# Grove_-_Recorder_v2_0.net
KiCad netlist of a schematic drawn in EAGLE
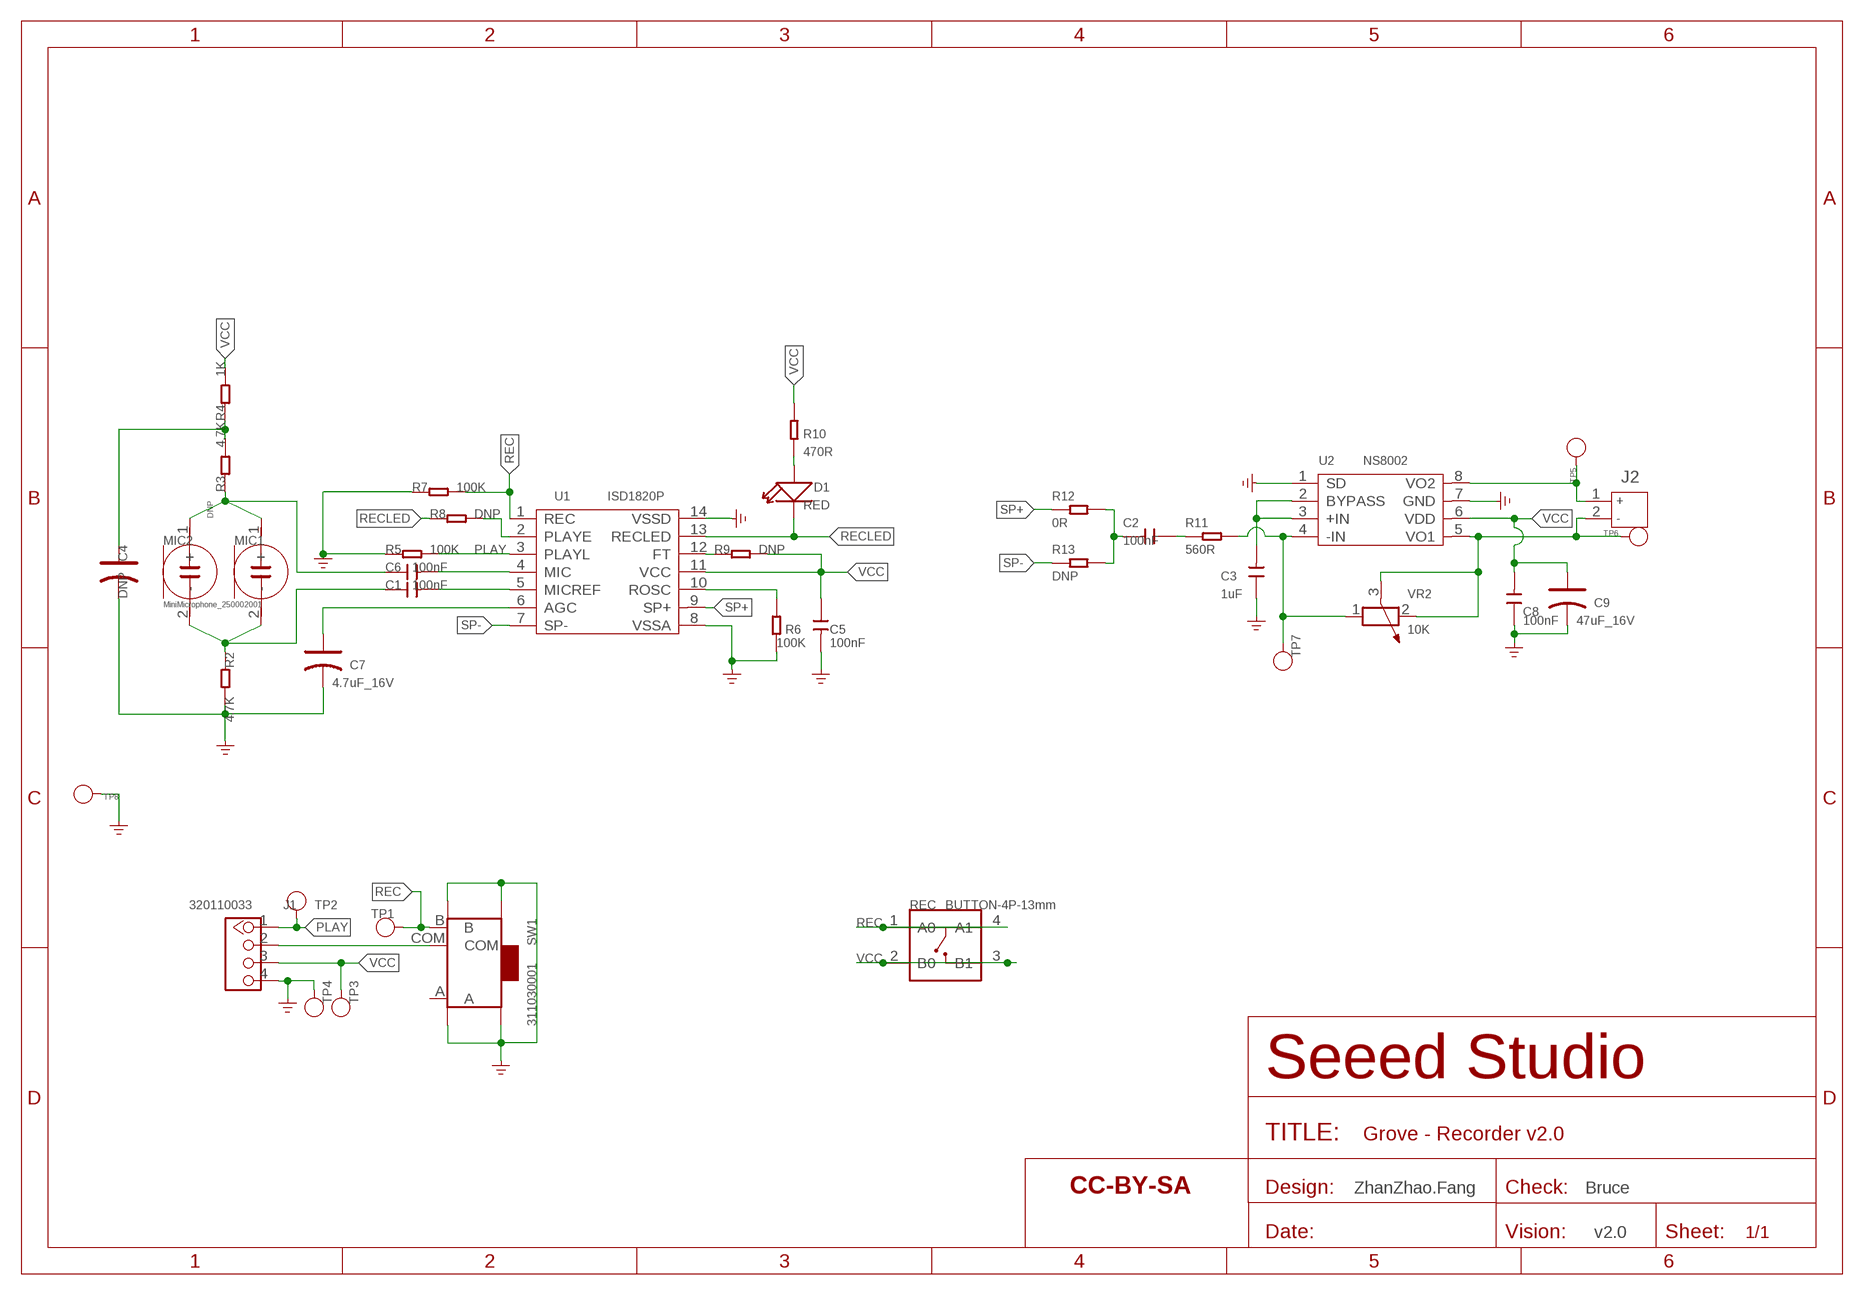
[diagram p0: schematic, sheet 1]

(export (version "E")
  (design (tool "Eeschema 10.0.6"))
  (components
    (comp (ref "C1")
      (value "100nF")
      (footprint "eagle-import:C0402")
      (libsource (lib "eagle-import") (part "C-0402"))
    )
    (comp (ref "C2")
      (value "100nF")
      (footprint "eagle-import:C0603")
      (libsource (lib "eagle-import") (part "CAP-0603"))
    )
    (comp (ref "C3")
      (value "1uF")
      (footprint "eagle-import:C0402")
      (libsource (lib "eagle-import") (part "CAP-0402"))
    )
    (comp (ref "C4")
      (value "DNP")
      (footprint "eagle-import:AVX-A")
      (libsource (lib "eagle-import") (part "CAP-AVX-A"))
    )
    (comp (ref "C5")
      (value "100nF")
      (footprint "eagle-import:C0402")
      (libsource (lib "eagle-import") (part "C-0402"))
    )
    (comp (ref "C6")
      (value "100nF")
      (footprint "eagle-import:C0402")
      (libsource (lib "eagle-import") (part "C-0402"))
    )
    (comp (ref "C7")
      (value "4.7uF_16V")
      (footprint "eagle-import:AVX-A")
      (libsource (lib "eagle-import") (part "C-POLAR-A"))
    )
    (comp (ref "C8")
      (value "100nF")
      (footprint "eagle-import:C0402")
      (libsource (lib "eagle-import") (part "CAP-0402"))
    )
    (comp (ref "C9")
      (value "47uF_16V")
      (footprint "eagle-import:AVX-B")
      (libsource (lib "eagle-import") (part "C-POLAR-B"))
    )
    (comp (ref "D1")
      (value "RED")
      (footprint "eagle-import:LED-SIDE-VIEW-0603-RIGHT")
      (libsource (lib "eagle-import") (part "LED'RIGHT'"))
    )
    (comp (ref "FR1")
      (value "SEEEDSTUDIO-OPEN-SCH-FRAME")
      (footprint "eagle-import:SEEEDSTUDIO-PCB-FRAME")
      (libsource (lib "eagle-import") (part "SEEEDSTUDIO-OPEN-SCH-FRAME"))
    )
    (comp (ref "J1")
      (value "320110033")
      (footprint "eagle-import:HW4-2.0")
      (libsource (lib "eagle-import") (part "GROVE-CONNECTOR-DIP-2.0"))
    )
    (comp (ref "J2")
      (value "2P-2.0")
      (footprint "eagle-import:JST-2.0")
      (libsource (lib "eagle-import") (part "JACK-JST-2P-PW'2.0'"))
    )
    (comp (ref "MIC1")
      (value "MiniMicrophone_250002001")
      (footprint "eagle-import:2P-D8.9MM")
      (libsource (lib "eagle-import") (part "MICROPHONE"))
    )
    (comp (ref "MIC2")
      (value "DNP")
      (footprint "eagle-import:2P-D8.9MM")
      (libsource (lib "eagle-import") (part "MICROPHONE"))
    )
    (comp (ref "R2")
      (value "4.7K")
      (footprint "eagle-import:R0402")
      (libsource (lib "eagle-import") (part "R-0402"))
    )
    (comp (ref "R3")
      (value "4.7K")
      (footprint "eagle-import:R0402")
      (libsource (lib "eagle-import") (part "R-0402"))
    )
    (comp (ref "R4")
      (value "1K")
      (footprint "eagle-import:R0402")
      (libsource (lib "eagle-import") (part "R-0402"))
    )
    (comp (ref "R5")
      (value "100K")
      (footprint "eagle-import:R0402")
      (libsource (lib "eagle-import") (part "R-0402"))
    )
    (comp (ref "R6")
      (value "100K")
      (footprint "eagle-import:R0402")
      (libsource (lib "eagle-import") (part "R-0402"))
    )
    (comp (ref "R7")
      (value "100K")
      (footprint "eagle-import:R0402")
      (libsource (lib "eagle-import") (part "R-0402"))
    )
    (comp (ref "R8")
      (value "DNP")
      (footprint "eagle-import:R0402")
      (libsource (lib "eagle-import") (part "R-0402"))
    )
    (comp (ref "R9")
      (value "DNP")
      (footprint "eagle-import:R0402")
      (libsource (lib "eagle-import") (part "R-0402"))
    )
    (comp (ref "R10")
      (value "470R")
      (footprint "eagle-import:R0402")
      (libsource (lib "eagle-import") (part "R-0402"))
    )
    (comp (ref "R11")
      (value "560R")
      (footprint "eagle-import:R0402")
      (libsource (lib "eagle-import") (part "RES-0402"))
    )
    (comp (ref "R12")
      (value "0R")
      (footprint "eagle-import:R0402")
      (libsource (lib "eagle-import") (part "R-0402"))
    )
    (comp (ref "R13")
      (value "DNP")
      (footprint "eagle-import:R0402")
      (libsource (lib "eagle-import") (part "R-0402"))
    )
    (comp (ref "REC")
      (value "BUTTON-4P-13mm")
      (footprint "eagle-import:4P-6.0X6.0X5.0H")
      (libsource (lib "eagle-import") (part "BUTTON-4P-3110040P1"))
    )
    (comp (ref "SW1")
      (value "311030001")
      (footprint "eagle-import:SW7-SMD-L6.7X2.7X3.2MM")
      (libsource (lib "eagle-import") (part "SWITCH-3+4P"))
    )
    (comp (ref "TP1")
      (value "DNP")
      (footprint "eagle-import:TP-D45MIL")
      (libsource (lib "eagle-import") (part "TEST-POINT'4545'"))
    )
    (comp (ref "TP2")
      (value "DNP")
      (footprint "eagle-import:TP-D45MIL")
      (libsource (lib "eagle-import") (part "TEST-POINT'4545'"))
    )
    (comp (ref "TP3")
      (value "DNP")
      (footprint "eagle-import:TP-D45MIL")
      (libsource (lib "eagle-import") (part "TEST-POINT'4545'"))
    )
    (comp (ref "TP4")
      (value "DNP")
      (footprint "eagle-import:TP-D45MIL")
      (libsource (lib "eagle-import") (part "TEST-POINT'4545'"))
    )
    (comp (ref "TP5")
      (value "DNP")
      (footprint "eagle-import:TP_4545")
      (libsource (lib "eagle-import") (part "PAD-TEST-POINT'4545'"))
    )
    (comp (ref "TP6")
      (value "DNP")
      (footprint "eagle-import:TP_4545")
      (libsource (lib "eagle-import") (part "PAD-TEST-POINT'4545'"))
    )
    (comp (ref "TP7")
      (value "DNP")
      (footprint "eagle-import:TP-D45MIL")
      (libsource (lib "eagle-import") (part "TEST-POINT'4545'"))
    )
    (comp (ref "TP8")
      (value "DNP")
      (footprint "eagle-import:TP_4545")
      (libsource (lib "eagle-import") (part "PAD-TEST-POINT'4545'"))
    )
    (comp (ref "U1")
      (value "ISD1820P")
      (footprint "eagle-import:DIP14")
      (libsource (lib "eagle-import") (part "ISD1820P"))
    )
    (comp (ref "U2")
      (value "NS8002")
      (footprint "eagle-import:SOIC8-1.27-5X4MM")
      (libsource (lib "eagle-import") (part "AMPLIFIER-NS8002"))
    )
    (comp (ref "VR2")
      (value "10K")
      (footprint "eagle-import:ADJR3-7.0X7.0X5.0MM")
      (libsource (lib "eagle-import") (part "RES-ADJ-SX3362P"))
    )
  )
  (nets
    (net (code "1") (name "GND_POWER") (class "Default")
      (node (ref "C3") (pin "1") (pinfunction "1_1") (pintype "passive"))
      (node (ref "C4") (pin "-") (pinfunction "-_-") (pintype "passive"))
      (node (ref "C5") (pin "2") (pinfunction "2_2") (pintype "passive"))
      (node (ref "C7") (pin "-") (pinfunction "2_-") (pintype "bidirectional"))
      (node (ref "C8") (pin "1") (pinfunction "1_1") (pintype "passive"))
      (node (ref "C9") (pin "-") (pinfunction "2_-") (pintype "bidirectional"))
      (node (ref "J1") (pin "4") (pinfunction "4_4") (pintype "bidirectional"))
      (node (ref "R2") (pin "2") (pinfunction "2_2") (pintype "passive"))
      (node (ref "R5") (pin "1") (pinfunction "1_1") (pintype "passive"))
      (node (ref "R6") (pin "1") (pinfunction "1_1") (pintype "passive"))
      (node (ref "R7") (pin "1") (pinfunction "1_1") (pintype "passive"))
      (node (ref "SW1") (pin "SS1") (pinfunction "SS1_SS1") (pintype "bidirectional"))
      (node (ref "SW1") (pin "SS2") (pinfunction "SS2_SS2") (pintype "bidirectional"))
      (node (ref "SW1") (pin "SS3") (pinfunction "SS3_SS3") (pintype "bidirectional"))
      (node (ref "SW1") (pin "SS4") (pinfunction "SS4_SS4") (pintype "bidirectional"))
      (node (ref "TP4") (pin "T") (pinfunction "T_T") (pintype "bidirectional"))
      (node (ref "TP8") (pin "T") (pinfunction "T_T") (pintype "bidirectional"))
      (node (ref "U1") (pin "14") (pinfunction "VSSD_14") (pintype "bidirectional"))
      (node (ref "U1") (pin "8") (pinfunction "VSSA_8") (pintype "bidirectional"))
      (node (ref "U2") (pin "1") (pinfunction "SD_1") (pintype "bidirectional"))
      (node (ref "U2") (pin "7") (pinfunction "GND_7") (pintype "power_in"))
    )
    (net (code "2") (name "Net-(C2-Pad1)") (class "Default")
      (node (ref "C2") (pin "1") (pinfunction "1_1") (pintype "passive"))
      (node (ref "R11") (pin "1") (pinfunction "1_1") (pintype "passive"))
    )
    (net (code "3") (name "Net-(C2-Pad2)") (class "Default")
      (node (ref "C2") (pin "2") (pinfunction "2_2") (pintype "passive"))
      (node (ref "R12") (pin "1") (pinfunction "1_1") (pintype "passive"))
      (node (ref "R13") (pin "1") (pinfunction "1_1") (pintype "passive"))
    )
    (net (code "4") (name "Net-(C4-Pad+)") (class "Default")
      (node (ref "C4") (pin "+") (pinfunction "+_+") (pintype "passive"))
      (node (ref "R3") (pin "2") (pinfunction "2_2") (pintype "passive"))
      (node (ref "R4") (pin "1") (pinfunction "1_1") (pintype "passive"))
    )
    (net (code "5") (name "Net-(C7-1)") (class "Default")
      (node (ref "C7") (pin "+") (pinfunction "1_+") (pintype "bidirectional"))
      (node (ref "U1") (pin "6") (pinfunction "AGC_6") (pintype "bidirectional"))
    )
    (net (code "6") (name "Net-(D1-+)") (class "Default")
      (node (ref "D1") (pin "1") (pinfunction "+_1") (pintype "passive"))
      (node (ref "R10") (pin "1") (pinfunction "1_1") (pintype "passive"))
    )
    (net (code "7") (name "Net-(J1-Pad2)") (class "Default")
      (node (ref "J1") (pin "2") (pinfunction "2_2") (pintype "bidirectional"))
      (node (ref "SW1") (pin "COM") (pinfunction "COM_COM") (pintype "bidirectional"))
    )
    (net (code "8") (name "Net-(J2-P$1)") (class "Default")
      (node (ref "J2") (pin "1") (pinfunction "P$1_1") (pintype "bidirectional"))
      (node (ref "TP5") (pin "T") (pinfunction "T_T") (pintype "bidirectional"))
      (node (ref "U2") (pin "8") (pinfunction "VO2_8") (pintype "output"))
    )
    (net (code "9") (name "Net-(J2-P$2)") (class "Default")
      (node (ref "J2") (pin "2") (pinfunction "P$2_2") (pintype "bidirectional"))
      (node (ref "TP6") (pin "T") (pinfunction "T_T") (pintype "bidirectional"))
      (node (ref "U2") (pin "5") (pinfunction "VO1_5") (pintype "output"))
      (node (ref "VR2") (pin "2") (pinfunction "2_2") (pintype "passive"))
      (node (ref "VR2") (pin "3") (pinfunction "3_3") (pintype "passive"))
    )
    (net (code "10") (name "Net-(MIC1-+)") (class "Default")
      (node (ref "C6") (pin "1") (pinfunction "1_1") (pintype "passive"))
      (node (ref "MIC1") (pin "1") (pinfunction "+_1") (pintype "bidirectional"))
      (node (ref "MIC2") (pin "1") (pinfunction "+_1") (pintype "bidirectional"))
      (node (ref "R3") (pin "1") (pinfunction "1_1") (pintype "passive"))
    )
    (net (code "11") (name "Net-(MIC1--)") (class "Default")
      (node (ref "C1") (pin "1") (pinfunction "1_1") (pintype "passive"))
      (node (ref "MIC1") (pin "2") (pinfunction "-_2") (pintype "bidirectional"))
      (node (ref "MIC2") (pin "2") (pinfunction "-_2") (pintype "bidirectional"))
      (node (ref "R2") (pin "1") (pinfunction "1_1") (pintype "passive"))
    )
    (net (code "12") (name "Net-(U1-FT)") (class "Default")
      (node (ref "R9") (pin "1") (pinfunction "1_1") (pintype "passive"))
      (node (ref "U1") (pin "12") (pinfunction "FT_12") (pintype "bidirectional"))
    )
    (net (code "13") (name "Net-(U1-MIC)") (class "Default")
      (node (ref "C6") (pin "2") (pinfunction "2_2") (pintype "passive"))
      (node (ref "U1") (pin "4") (pinfunction "MIC_4") (pintype "bidirectional"))
    )
    (net (code "14") (name "Net-(U1-MICREF)") (class "Default")
      (node (ref "C1") (pin "2") (pinfunction "2_2") (pintype "passive"))
      (node (ref "U1") (pin "5") (pinfunction "MICREF_5") (pintype "bidirectional"))
    )
    (net (code "15") (name "Net-(U1-PLAYE)") (class "Default")
      (node (ref "R8") (pin "2") (pinfunction "2_2") (pintype "passive"))
      (node (ref "U1") (pin "2") (pinfunction "PLAYE_2") (pintype "bidirectional"))
    )
    (net (code "16") (name "Net-(U1-ROSC)") (class "Default")
      (node (ref "R6") (pin "2") (pinfunction "2_2") (pintype "passive"))
      (node (ref "U1") (pin "10") (pinfunction "ROSC_10") (pintype "bidirectional"))
    )
    (net (code "17") (name "Net-(U2-+IN)") (class "Default")
      (node (ref "C3") (pin "2") (pinfunction "2_2") (pintype "passive"))
      (node (ref "U2") (pin "2") (pinfunction "BYPASS_2") (pintype "bidirectional"))
      (node (ref "U2") (pin "3") (pinfunction "+IN_3") (pintype "input"))
    )
    (net (code "18") (name "Net-(U2--IN)") (class "Default")
      (node (ref "R11") (pin "2") (pinfunction "2_2") (pintype "passive"))
      (node (ref "TP7") (pin "T") (pinfunction "T_T") (pintype "bidirectional"))
      (node (ref "U2") (pin "4") (pinfunction "-IN_4") (pintype "input"))
      (node (ref "VR2") (pin "1") (pinfunction "1_1") (pintype "passive"))
    )
    (net (code "19") (name "PLAY") (class "Default")
      (node (ref "J1") (pin "1") (pinfunction "1_1") (pintype "bidirectional"))
      (node (ref "R5") (pin "2") (pinfunction "2_2") (pintype "passive"))
      (node (ref "TP2") (pin "T") (pinfunction "T_T") (pintype "bidirectional"))
      (node (ref "U1") (pin "3") (pinfunction "PLAYL_3") (pintype "bidirectional"))
    )
    (net (code "20") (name "REC") (class "Default")
      (node (ref "R7") (pin "2") (pinfunction "2_2") (pintype "passive"))
      (node (ref "REC") (pin "1") (pinfunction "A0_1") (pintype "bidirectional"))
      (node (ref "REC") (pin "4") (pinfunction "A1_4") (pintype "bidirectional"))
      (node (ref "SW1") (pin "B") (pinfunction "B_B") (pintype "bidirectional"))
      (node (ref "TP1") (pin "T") (pinfunction "T_T") (pintype "bidirectional"))
      (node (ref "U1") (pin "1") (pinfunction "REC_1") (pintype "bidirectional"))
    )
    (net (code "21") (name "RECLED") (class "Default")
      (node (ref "D1") (pin "2") (pinfunction "-_2") (pintype "passive"))
      (node (ref "R8") (pin "1") (pinfunction "1_1") (pintype "passive"))
      (node (ref "U1") (pin "13") (pinfunction "RECLED_13") (pintype "bidirectional"))
    )
    (net (code "22") (name "SP+") (class "Default")
      (node (ref "R12") (pin "2") (pinfunction "2_2") (pintype "passive"))
      (node (ref "U1") (pin "9") (pinfunction "SP+_9") (pintype "bidirectional"))
    )
    (net (code "23") (name "SP-") (class "Default")
      (node (ref "R13") (pin "2") (pinfunction "2_2") (pintype "passive"))
      (node (ref "U1") (pin "7") (pinfunction "SP-_7") (pintype "bidirectional"))
    )
    (net (code "24") (name "VCC") (class "Default")
      (node (ref "C5") (pin "1") (pinfunction "1_1") (pintype "passive"))
      (node (ref "C8") (pin "2") (pinfunction "2_2") (pintype "passive"))
      (node (ref "C9") (pin "+") (pinfunction "1_+") (pintype "bidirectional"))
      (node (ref "J1") (pin "3") (pinfunction "3_3") (pintype "bidirectional"))
      (node (ref "R10") (pin "2") (pinfunction "2_2") (pintype "passive"))
      (node (ref "R4") (pin "2") (pinfunction "2_2") (pintype "passive"))
      (node (ref "R9") (pin "2") (pinfunction "2_2") (pintype "passive"))
      (node (ref "REC") (pin "2") (pinfunction "B0_2") (pintype "bidirectional"))
      (node (ref "REC") (pin "3") (pinfunction "B1_3") (pintype "bidirectional"))
      (node (ref "TP3") (pin "T") (pinfunction "T_T") (pintype "bidirectional"))
      (node (ref "U1") (pin "11") (pinfunction "VCC_11") (pintype "bidirectional"))
      (node (ref "U2") (pin "6") (pinfunction "VDD_6") (pintype "power_in"))
    )
    (net (code "25") (name "unconnected-(SW1-PadA)") (class "Default")
      (node (ref "SW1") (pin "A") (pinfunction "A_A") (pintype "bidirectional"))
    )
  )
)
